# design.net
KiCad netlist of a schematic drawn in EAGLE
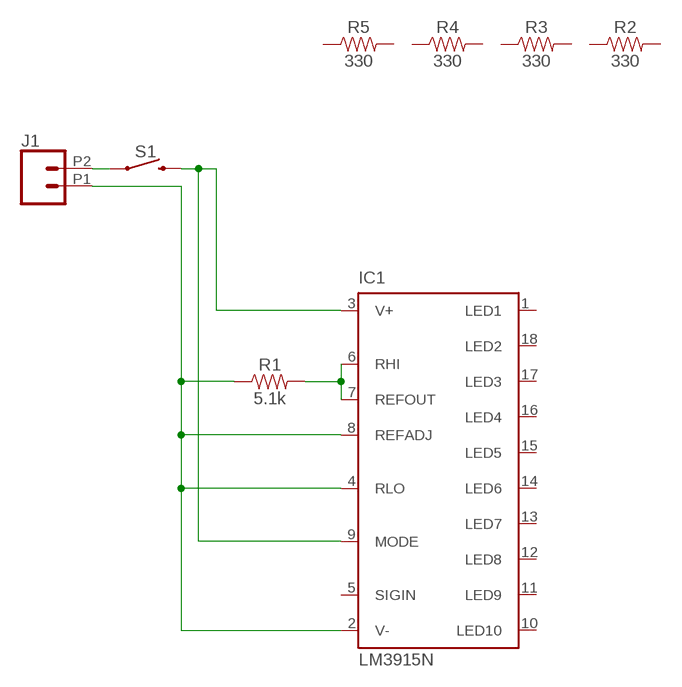
[diagram p0: schematic, sheet 1]

(export (version "E")
  (design (tool "Eeschema 10.0.6"))
  (components
    (comp (ref "IC1")
      (value "LM3915N")
      (footprint "eagle-import:DIL18")
      (libsource (lib "eagle-import") (part "LM391N5"))
    )
    (comp (ref "J1")
      (value "CONN_022.54MM_SCREWTERM")
      (footprint "eagle-import:1X02_2.54_SCREWTERM")
      (libsource (lib "eagle-import") (part "CONN_022.54MM_SCREWTERM"))
    )
    (comp (ref "R1")
      (value "5.1k")
      (footprint "eagle-import:AXIAL-0.3")
      (libsource (lib "eagle-import") (part "330OHM-HORIZ-1/10W-5%"))
    )
    (comp (ref "R2")
      (value "330")
      (footprint "eagle-import:AXIAL-0.3")
      (libsource (lib "eagle-import") (part "330OHM-HORIZ-1/10W-5%"))
    )
    (comp (ref "R3")
      (value "330")
      (footprint "eagle-import:AXIAL-0.3")
      (libsource (lib "eagle-import") (part "330OHM-HORIZ-1/10W-5%"))
    )
    (comp (ref "R4")
      (value "330")
      (footprint "eagle-import:AXIAL-0.3")
      (libsource (lib "eagle-import") (part "330OHM-HORIZ-1/10W-5%"))
    )
    (comp (ref "R5")
      (value "330")
      (footprint "eagle-import:AXIAL-0.3")
      (libsource (lib "eagle-import") (part "330OHM-HORIZ-1/10W-5%"))
    )
    (comp (ref "S1")
      (value "MOMENTARY-SWITCH-SPST-PTH-6.0MM")
      (footprint "eagle-import:TACTILE_SWITCH_PTH_6.0MM")
      (libsource (lib "eagle-import") (part "MOMENTARY-SWITCH-SPST-PTH-6.0MM"))
    )
  )
  (nets
    (net (code "1") (name "Net-(IC1-MODE)") (class "Default")
      (node (ref "IC1") (pin "3") (pinfunction "V+_3") (pintype "power_in"))
      (node (ref "IC1") (pin "9") (pinfunction "MODE_9") (pintype "input"))
      (node (ref "S1") (pin "3") (pinfunction "2_3") (pintype "passive"))
    )
    (net (code "2") (name "Net-(IC1-REFADJ)") (class "Default")
      (node (ref "IC1") (pin "2") (pinfunction "V-_2") (pintype "power_in"))
      (node (ref "IC1") (pin "4") (pinfunction "RLO_4") (pintype "input"))
      (node (ref "IC1") (pin "8") (pinfunction "REFADJ_8") (pintype "passive"))
      (node (ref "J1") (pin "P1") (pinfunction "1_P1") (pintype "passive"))
      (node (ref "R1") (pin "P$1") (pinfunction "1_P$1") (pintype "passive"))
    )
    (net (code "3") (name "Net-(IC1-REFOUT)") (class "Default")
      (node (ref "IC1") (pin "6") (pinfunction "RHI_6") (pintype "input"))
      (node (ref "IC1") (pin "7") (pinfunction "REFOUT_7") (pintype "output"))
      (node (ref "R1") (pin "P$2") (pinfunction "2_P$2") (pintype "passive"))
    )
    (net (code "4") (name "Net-(J1-2)") (class "Default")
      (node (ref "J1") (pin "P2") (pinfunction "2_P2") (pintype "passive"))
      (node (ref "S1") (pin "1") (pinfunction "1_1") (pintype "passive"))
    )
    (net (code "5") (name "unconnected-(IC1-LED1-Pad1)") (class "Default")
      (node (ref "IC1") (pin "1") (pinfunction "LED1_1") (pintype "output"))
    )
    (net (code "6") (name "unconnected-(IC1-LED2-Pad18)") (class "Default")
      (node (ref "IC1") (pin "18") (pinfunction "LED2_18") (pintype "output"))
    )
    (net (code "7") (name "unconnected-(IC1-LED3-Pad17)") (class "Default")
      (node (ref "IC1") (pin "17") (pinfunction "LED3_17") (pintype "output"))
    )
    (net (code "8") (name "unconnected-(IC1-LED4-Pad16)") (class "Default")
      (node (ref "IC1") (pin "16") (pinfunction "LED4_16") (pintype "output"))
    )
    (net (code "9") (name "unconnected-(IC1-LED5-Pad15)") (class "Default")
      (node (ref "IC1") (pin "15") (pinfunction "LED5_15") (pintype "output"))
    )
    (net (code "10") (name "unconnected-(IC1-LED6-Pad14)") (class "Default")
      (node (ref "IC1") (pin "14") (pinfunction "LED6_14") (pintype "output"))
    )
    (net (code "11") (name "unconnected-(IC1-LED7-Pad13)") (class "Default")
      (node (ref "IC1") (pin "13") (pinfunction "LED7_13") (pintype "output"))
    )
    (net (code "12") (name "unconnected-(IC1-LED8-Pad12)") (class "Default")
      (node (ref "IC1") (pin "12") (pinfunction "LED8_12") (pintype "output"))
    )
    (net (code "13") (name "unconnected-(IC1-LED9-Pad11)") (class "Default")
      (node (ref "IC1") (pin "11") (pinfunction "LED9_11") (pintype "output"))
    )
    (net (code "14") (name "unconnected-(IC1-LED10-Pad10)") (class "Default")
      (node (ref "IC1") (pin "10") (pinfunction "LED10_10") (pintype "output"))
    )
    (net (code "15") (name "unconnected-(IC1-SIGIN-Pad5)") (class "Default")
      (node (ref "IC1") (pin "5") (pinfunction "SIGIN_5") (pintype "input"))
    )
    (net (code "16") (name "unconnected-(R2-1-PadP$1)") (class "Default")
      (node (ref "R2") (pin "P$1") (pinfunction "1_P$1") (pintype "passive"))
    )
    (net (code "17") (name "unconnected-(R2-2-PadP$2)") (class "Default")
      (node (ref "R2") (pin "P$2") (pinfunction "2_P$2") (pintype "passive"))
    )
    (net (code "18") (name "unconnected-(R3-1-PadP$1)") (class "Default")
      (node (ref "R3") (pin "P$1") (pinfunction "1_P$1") (pintype "passive"))
    )
    (net (code "19") (name "unconnected-(R3-2-PadP$2)") (class "Default")
      (node (ref "R3") (pin "P$2") (pinfunction "2_P$2") (pintype "passive"))
    )
    (net (code "20") (name "unconnected-(R4-1-PadP$1)") (class "Default")
      (node (ref "R4") (pin "P$1") (pinfunction "1_P$1") (pintype "passive"))
    )
    (net (code "21") (name "unconnected-(R4-2-PadP$2)") (class "Default")
      (node (ref "R4") (pin "P$2") (pinfunction "2_P$2") (pintype "passive"))
    )
    (net (code "22") (name "unconnected-(R5-1-PadP$1)") (class "Default")
      (node (ref "R5") (pin "P$1") (pinfunction "1_P$1") (pintype "passive"))
    )
    (net (code "23") (name "unconnected-(R5-2-PadP$2)") (class "Default")
      (node (ref "R5") (pin "P$2") (pinfunction "2_P$2") (pintype "passive"))
    )
  )
)
